# EntradaSensores.net
KiCad netlist of a schematic drawn in Altium Designer
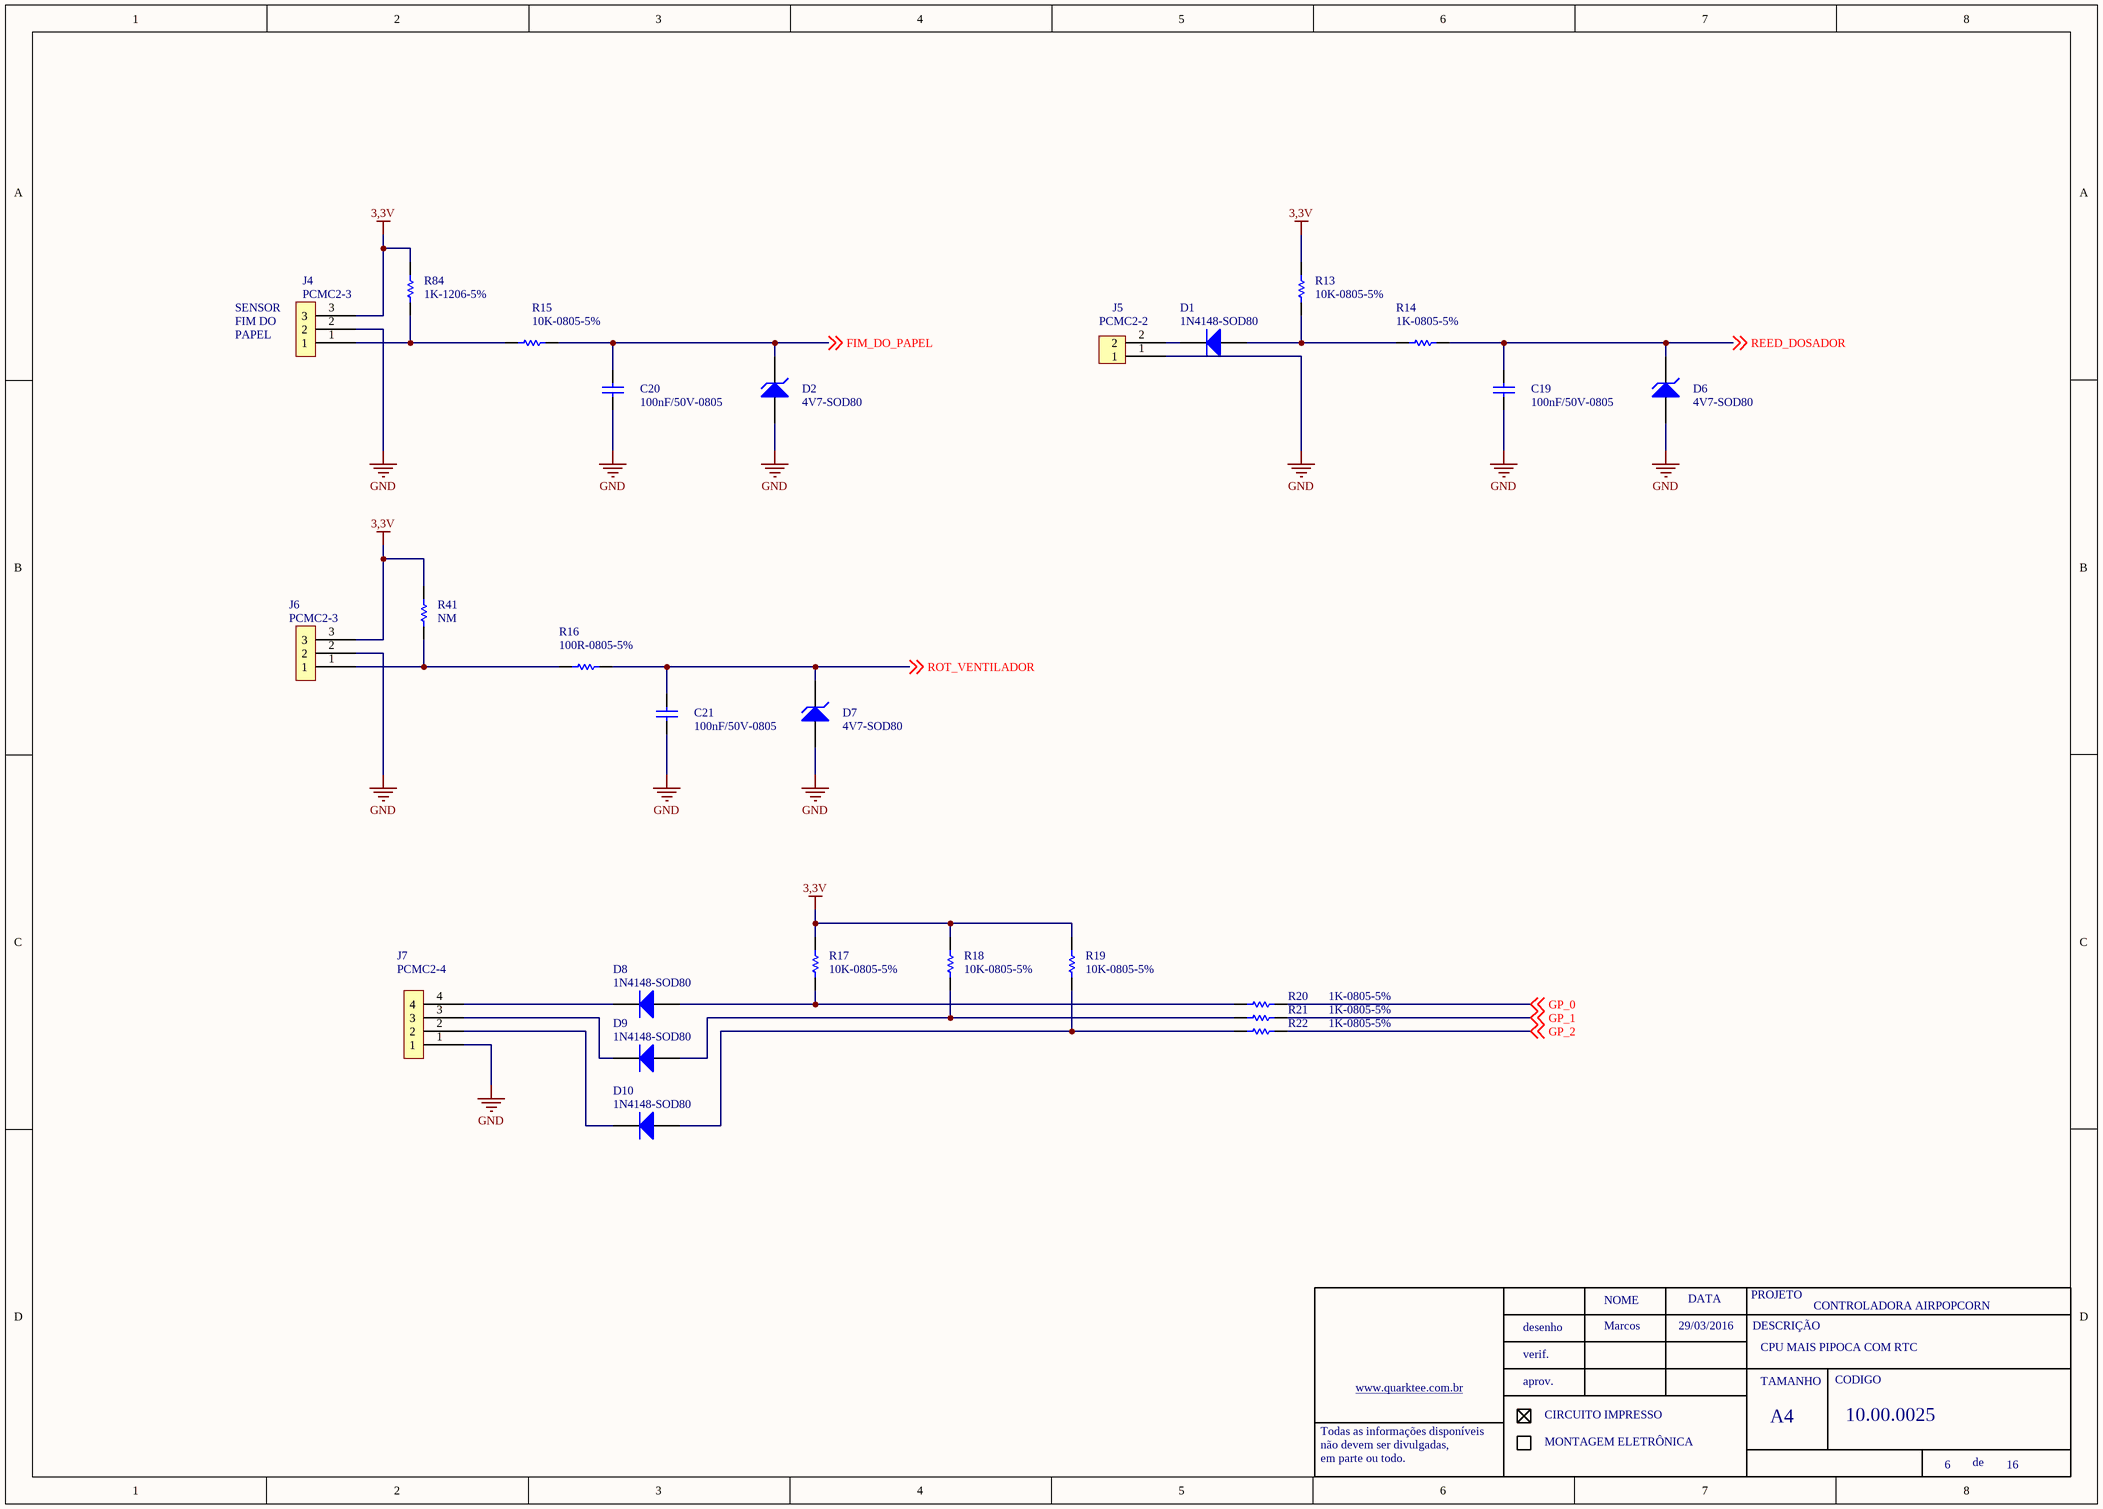
[diagram p0: EntradaSensores.SchDoc]

(export (version "E")
  (design (tool "Eeschema 10.0.6"))
  (components
    (comp (ref "C19")
      (value "100nF/50V-0805")
      (footprint "0805-REVISADO O")
      (description "100nF/50-0805-NPO")
      (libsource (lib "AquinoLib") (part "100nF/50-0805-NPO"))
    )
    (comp (ref "C20")
      (value "100nF/50V-0805")
      (footprint "0805-REVISADO O")
      (description "100nF/50-0805-NPO")
      (libsource (lib "AquinoLib") (part "100nF/50-0805-NPO"))
    )
    (comp (ref "C21")
      (value "100nF/50V-0805")
      (footprint "0805-REVISADO O")
      (description "10nF/50V-0805-NPO")
      (libsource (lib "AquinoLib") (part "10nF/50V-0805-NPO"))
    )
    (comp (ref "D1")
      (value "1N4148-SOD80")
      (footprint "MINIMLEF/SOD80")
      (libsource (lib "AquinoLib") (part "1N4148-SOD80"))
    )
    (comp (ref "D2")
      (value "4V7-SOD80")
      (footprint "MINIMLEF/SOD80")
      (description "3V3-SOD80-1/2W")
      (libsource (lib "AquinoLib") (part "ZENER 3V3-SOD80"))
    )
    (comp (ref "D6")
      (value "4V7-SOD80")
      (footprint "MINIMLEF/SOD80")
      (description "3V3-SOD80-1/2W")
      (libsource (lib "AquinoLib") (part "ZENER 3V3-SOD80"))
    )
    (comp (ref "D7")
      (value "4V7-SOD80")
      (footprint "MINIMLEF/SOD80")
      (description "3V3-SOD80-1/2W")
      (libsource (lib "AquinoLib") (part "ZENER 3V3-SOD80"))
    )
    (comp (ref "D8")
      (value "1N4148-SOD80")
      (footprint "MINIMLEF/SOD80")
      (libsource (lib "AquinoLib") (part "1N4148-SOD80"))
    )
    (comp (ref "D9")
      (value "1N4148-SOD80")
      (footprint "MINIMLEF/SOD80")
      (libsource (lib "AquinoLib") (part "1N4148-SOD80"))
    )
    (comp (ref "D10")
      (value "1N4148-SOD80")
      (footprint "MINIMLEF/SOD80")
      (libsource (lib "AquinoLib") (part "1N4148-SOD80"))
    )
    (comp (ref "J4") (value "PCMC2-3") (footprint "PCMC2-3") (libsource (lib "AquinoLib") (part "PCMC2-3")))
    (comp (ref "J5") (value "PCMC2-2") (footprint "PCMC2-2") (libsource (lib "AquinoLib") (part "PCMC2-2")))
    (comp (ref "J6") (value "PCMC2-3") (footprint "PCMC2-3") (libsource (lib "AquinoLib") (part "PCMC2-3")))
    (comp (ref "J7") (value "PCMC2-4") (footprint "PCMC2-4") (libsource (lib "AquinoLib") (part "PCMC2-4")))
    (comp (ref "R13")
      (value "10K-0805-5%")
      (footprint "0805-REVISADO O")
      (libsource (lib "AquinoLib") (part "10K-0805-5%"))
    )
    (comp (ref "R14")
      (value "1K-0805-5%")
      (footprint "0805-REVISADO O")
      (libsource (lib "AquinoLib") (part "1K-0805-5%"))
    )
    (comp (ref "R15")
      (value "10K-0805-5%")
      (footprint "0805-REVISADO O")
      (description "100K-0805-5%")
      (libsource (lib "AquinoLib") (part "100K-0805-5%"))
    )
    (comp (ref "R16")
      (value "100R-0805-5%")
      (footprint "0805-REVISADO O")
      (description "100K-0805-5%")
      (libsource (lib "AquinoLib") (part "100K-0805-5%"))
    )
    (comp (ref "R17")
      (value "10K-0805-5%")
      (footprint "0805-REVISADO O")
      (libsource (lib "AquinoLib") (part "10K-0805-5%"))
    )
    (comp (ref "R18")
      (value "10K-0805-5%")
      (footprint "0805-REVISADO O")
      (libsource (lib "AquinoLib") (part "10K-0805-5%"))
    )
    (comp (ref "R19")
      (value "10K-0805-5%")
      (footprint "0805-REVISADO O")
      (libsource (lib "AquinoLib") (part "10K-0805-5%"))
    )
    (comp (ref "R20")
      (value "1K-0805-5%")
      (footprint "0805-REVISADO O")
      (description "10K-0805-5%")
      (libsource (lib "AquinoLib") (part "10K-0805-5%"))
    )
    (comp (ref "R21")
      (value "1K-0805-5%")
      (footprint "0805-REVISADO O")
      (description "10K-0805-5%")
      (libsource (lib "AquinoLib") (part "10K-0805-5%"))
    )
    (comp (ref "R22")
      (value "1K-0805-5%")
      (footprint "0805-REVISADO O")
      (description "10K-0805-5%")
      (libsource (lib "AquinoLib") (part "10K-0805-5%"))
    )
    (comp (ref "R41")
      (value "NM")
      (footprint "0805-REVISADO O")
      (description "100K-0805-5%")
      (libsource (lib "AquinoLib") (part "100K-0805-5%"))
    )
    (comp (ref "R84")
      (value "1K-1206-5%")
      (footprint "1206-REVISADO O")
      (description "1K-0805-5%")
      (libsource (lib "AquinoLib") (part "1K-0805-5%"))
    )
  )
  (nets
    (net (code "1") (name "3,3V") (class "Default")
      (node (ref "J4") (pin "3") (pinfunction "3_3") (pintype "passive"))
      (node (ref "J6") (pin "3") (pinfunction "3_3") (pintype "passive"))
      (node (ref "R13") (pin "2") (pinfunction "2_2") (pintype "passive"))
      (node (ref "R17") (pin "2") (pinfunction "2_2") (pintype "passive"))
      (node (ref "R18") (pin "2") (pinfunction "2_2") (pintype "passive"))
      (node (ref "R19") (pin "2") (pinfunction "2_2") (pintype "passive"))
      (node (ref "R41") (pin "2") (pinfunction "2_2") (pintype "passive"))
      (node (ref "R84") (pin "2") (pinfunction "2_2") (pintype "passive"))
    )
    (net (code "2") (name "FIM_DO_PAPEL") (class "Default")
      (node (ref "C20") (pin "2") (pinfunction "2_2") (pintype "passive"))
      (node (ref "D2") (pin "2") (pinfunction "K_2") (pintype "passive"))
      (node (ref "R15") (pin "2") (pinfunction "2_2") (pintype "passive"))
    )
    (net (code "3") (name "GND") (class "Default")
      (node (ref "C19") (pin "1") (pinfunction "1_1") (pintype "passive"))
      (node (ref "C20") (pin "1") (pinfunction "1_1") (pintype "passive"))
      (node (ref "C21") (pin "1") (pinfunction "1_1") (pintype "passive"))
      (node (ref "D2") (pin "1") (pinfunction "A_1") (pintype "passive"))
      (node (ref "D6") (pin "1") (pinfunction "A_1") (pintype "passive"))
      (node (ref "D7") (pin "1") (pinfunction "A_1") (pintype "passive"))
      (node (ref "J4") (pin "2") (pinfunction "2_2") (pintype "passive"))
      (node (ref "J5") (pin "1") (pinfunction "1_1") (pintype "passive"))
      (node (ref "J6") (pin "2") (pinfunction "2_2") (pintype "passive"))
      (node (ref "J7") (pin "1") (pinfunction "1_1") (pintype "passive"))
    )
    (net (code "4") (name "GP_0") (class "Default")
      (node (ref "R20") (pin "2") (pinfunction "2_2") (pintype "passive"))
    )
    (net (code "5") (name "GP_1") (class "Default")
      (node (ref "R21") (pin "2") (pinfunction "2_2") (pintype "passive"))
    )
    (net (code "6") (name "GP_2") (class "Default")
      (node (ref "R22") (pin "2") (pinfunction "2_2") (pintype "passive"))
    )
    (net (code "7") (name "Net-(D1-Pad1)") (class "Default")
      (node (ref "D1") (pin "1") (pinfunction "1_1") (pintype "passive"))
      (node (ref "R13") (pin "1") (pinfunction "1_1") (pintype "passive"))
      (node (ref "R14") (pin "1") (pinfunction "1_1") (pintype "passive"))
    )
    (net (code "8") (name "Net-(D1-Pad2)") (class "Default")
      (node (ref "D1") (pin "2") (pinfunction "2_2") (pintype "passive"))
      (node (ref "J5") (pin "2") (pinfunction "2_2") (pintype "passive"))
    )
    (net (code "9") (name "Net-(D8-Pad1)") (class "Default")
      (node (ref "D8") (pin "1") (pinfunction "1_1") (pintype "passive"))
      (node (ref "R17") (pin "1") (pinfunction "1_1") (pintype "passive"))
      (node (ref "R20") (pin "1") (pinfunction "1_1") (pintype "passive"))
    )
    (net (code "10") (name "Net-(D8-Pad2)") (class "Default")
      (node (ref "D8") (pin "2") (pinfunction "2_2") (pintype "passive"))
      (node (ref "J7") (pin "4") (pinfunction "4_4") (pintype "passive"))
    )
    (net (code "11") (name "Net-(D9-Pad1)") (class "Default")
      (node (ref "D9") (pin "1") (pinfunction "1_1") (pintype "passive"))
      (node (ref "R18") (pin "1") (pinfunction "1_1") (pintype "passive"))
      (node (ref "R21") (pin "1") (pinfunction "1_1") (pintype "passive"))
    )
    (net (code "12") (name "Net-(D9-Pad2)") (class "Default")
      (node (ref "D9") (pin "2") (pinfunction "2_2") (pintype "passive"))
      (node (ref "J7") (pin "3") (pinfunction "3_3") (pintype "passive"))
    )
    (net (code "13") (name "Net-(D10-Pad1)") (class "Default")
      (node (ref "D10") (pin "1") (pinfunction "1_1") (pintype "passive"))
      (node (ref "R19") (pin "1") (pinfunction "1_1") (pintype "passive"))
      (node (ref "R22") (pin "1") (pinfunction "1_1") (pintype "passive"))
    )
    (net (code "14") (name "Net-(D10-Pad2)") (class "Default")
      (node (ref "D10") (pin "2") (pinfunction "2_2") (pintype "passive"))
      (node (ref "J7") (pin "2") (pinfunction "2_2") (pintype "passive"))
    )
    (net (code "15") (name "Net-(J4-Pad1)") (class "Default")
      (node (ref "J4") (pin "1") (pinfunction "1_1") (pintype "passive"))
      (node (ref "R15") (pin "1") (pinfunction "1_1") (pintype "passive"))
      (node (ref "R84") (pin "1") (pinfunction "1_1") (pintype "passive"))
    )
    (net (code "16") (name "Net-(J6-Pad1)") (class "Default")
      (node (ref "J6") (pin "1") (pinfunction "1_1") (pintype "passive"))
      (node (ref "R16") (pin "1") (pinfunction "1_1") (pintype "passive"))
      (node (ref "R41") (pin "1") (pinfunction "1_1") (pintype "passive"))
    )
    (net (code "17") (name "REED_DOSADOR") (class "Default")
      (node (ref "C19") (pin "2") (pinfunction "2_2") (pintype "passive"))
      (node (ref "D6") (pin "2") (pinfunction "K_2") (pintype "passive"))
      (node (ref "R14") (pin "2") (pinfunction "2_2") (pintype "passive"))
    )
    (net (code "18") (name "ROT_VENTILADOR") (class "Default")
      (node (ref "C21") (pin "2") (pinfunction "2_2") (pintype "passive"))
      (node (ref "D7") (pin "2") (pinfunction "K_2") (pintype "passive"))
      (node (ref "R16") (pin "2") (pinfunction "2_2") (pintype "passive"))
    )
  )
)
